# relay.net
KiCad netlist of a schematic drawn in Altium Designer
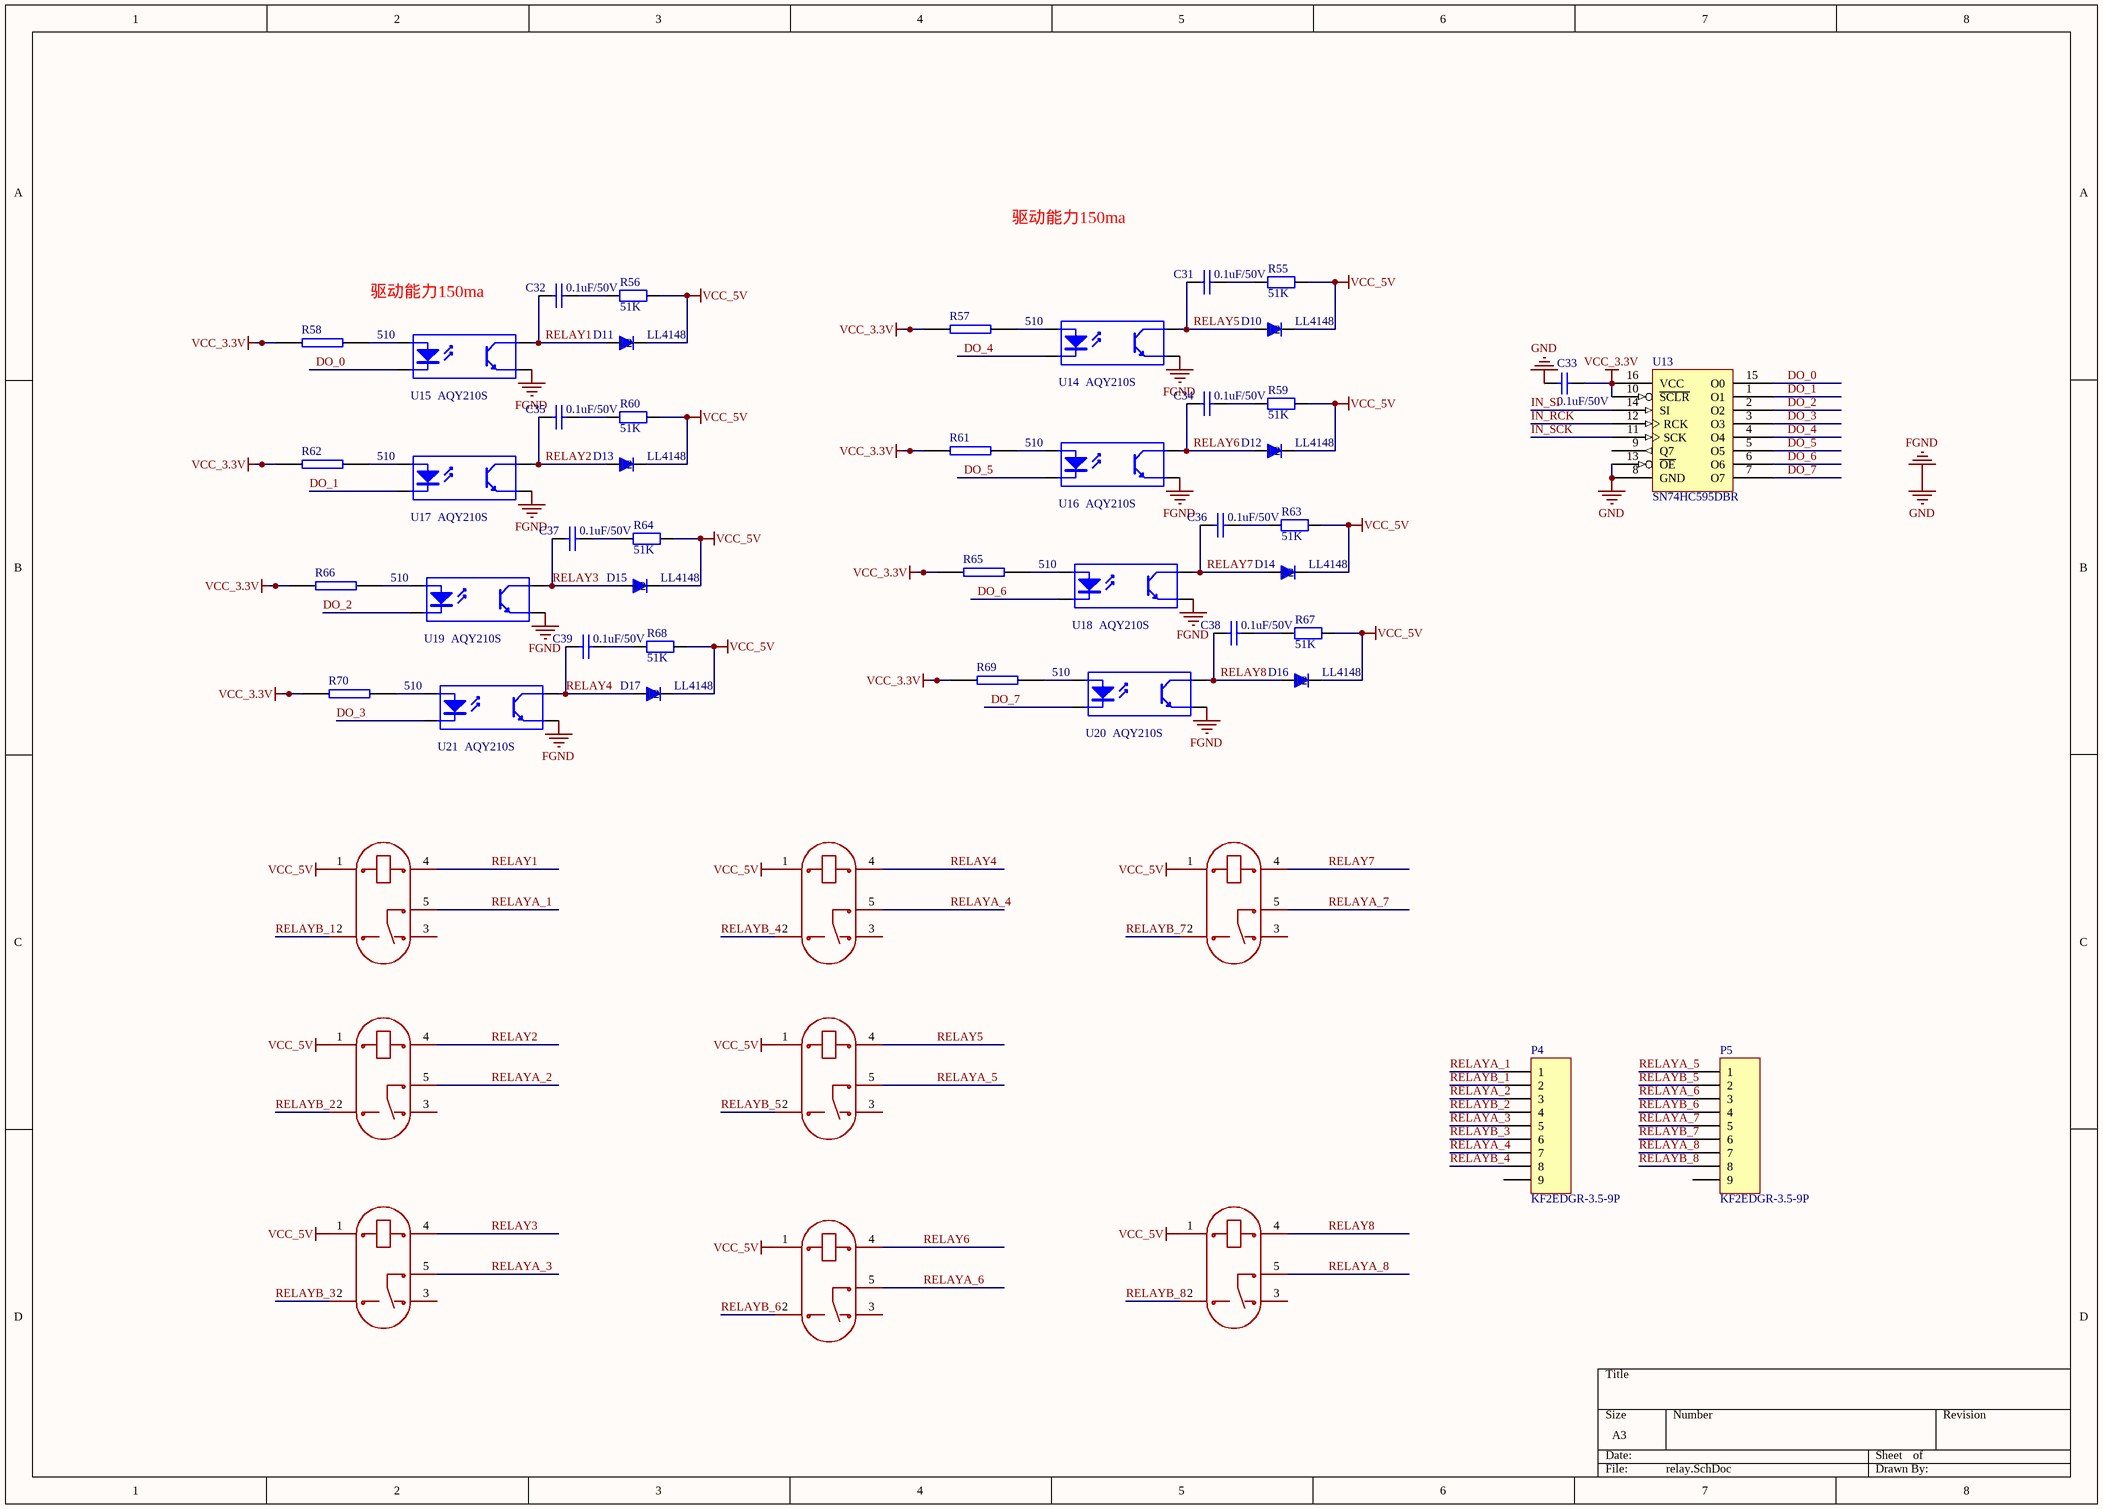
[diagram p0: relay.SchDoc]

(export (version "E")
  (design (tool "Eeschema 10.0.6"))
  (components
    (comp (ref "C31")
      (value "0.1uF/50V")
      (footprint "0603C")
      (description "Capacitor")
      (libsource (lib "*") (part "CAP"))
    )
    (comp (ref "C32")
      (value "0.1uF/50V")
      (footprint "0603C")
      (description "Capacitor")
      (libsource (lib "*") (part "CAP"))
    )
    (comp (ref "C33")
      (value "0.1uF/50V")
      (footprint "0603C")
      (description "Capacitor")
      (libsource (lib "Miscellaneous Devices") (part "Cap"))
    )
    (comp (ref "C34")
      (value "0.1uF/50V")
      (footprint "0603C")
      (description "Capacitor")
      (libsource (lib "*") (part "CAP"))
    )
    (comp (ref "C35")
      (value "0.1uF/50V")
      (footprint "0603C")
      (description "Capacitor")
      (libsource (lib "*") (part "CAP"))
    )
    (comp (ref "C36")
      (value "0.1uF/50V")
      (footprint "0603C")
      (description "Capacitor")
      (libsource (lib "*") (part "CAP"))
    )
    (comp (ref "C37")
      (value "0.1uF/50V")
      (footprint "0603C")
      (description "Capacitor")
      (libsource (lib "*") (part "CAP"))
    )
    (comp (ref "C38")
      (value "0.1uF/50V")
      (footprint "0603C")
      (description "Capacitor")
      (libsource (lib "*") (part "CAP"))
    )
    (comp (ref "C39")
      (value "0.1uF/50V")
      (footprint "0603C")
      (description "Capacitor")
      (libsource (lib "*") (part "CAP"))
    )
    (comp (ref "D10")
      (value "LL4148")
      (footprint "DO-213AB/LL34/MiniMELF")
      (description "VISHAY,LL4148,圆柱体MiniMELF100V/2A,ROHS")
      (libsource (lib "Device2018") (part "LL4148"))
    )
    (comp (ref "D11")
      (value "LL4148")
      (footprint "DO-213AB/LL34/MiniMELF")
      (description "VISHAY,LL4148,圆柱体MiniMELF100V/2A,ROHS")
      (libsource (lib "Device2018") (part "LL4148"))
    )
    (comp (ref "D12")
      (value "LL4148")
      (footprint "DO-213AB/LL34/MiniMELF")
      (description "VISHAY,LL4148,圆柱体MiniMELF100V/2A,ROHS")
      (libsource (lib "Device2018") (part "LL4148"))
    )
    (comp (ref "D13")
      (value "LL4148")
      (footprint "DO-213AB/LL34/MiniMELF")
      (description "VISHAY,LL4148,圆柱体MiniMELF100V/2A,ROHS")
      (libsource (lib "Device2018") (part "LL4148"))
    )
    (comp (ref "D14")
      (value "LL4148")
      (footprint "DO-213AB/LL34/MiniMELF")
      (description "VISHAY,LL4148,圆柱体MiniMELF100V/2A,ROHS")
      (libsource (lib "Device2018") (part "LL4148"))
    )
    (comp (ref "D15")
      (value "LL4148")
      (footprint "DO-213AB/LL34/MiniMELF")
      (description "VISHAY,LL4148,圆柱体MiniMELF100V/2A,ROHS")
      (libsource (lib "Device2018") (part "LL4148"))
    )
    (comp (ref "D16")
      (value "LL4148")
      (footprint "DO-213AB/LL34/MiniMELF")
      (description "VISHAY,LL4148,圆柱体MiniMELF100V/2A,ROHS")
      (libsource (lib "Device2018") (part "LL4148"))
    )
    (comp (ref "D17")
      (value "LL4148")
      (footprint "DO-213AB/LL34/MiniMELF")
      (description "VISHAY,LL4148,圆柱体MiniMELF100V/2A,ROHS")
      (libsource (lib "Device2018") (part "LL4148"))
    )
    (comp (ref "P4")
      (value "KF2EDGR-3.5-9P")
      (footprint "CONN-TH_9P-P3.50_KF2EDGR-3.5-9P:CONN-TH_9P-P3.50_KF2EDGR-3.5-9P")
      (description "Header, 9-Pin")
      (libsource (lib "Miscellaneous Connectors") (part "Header 9"))
    )
    (comp (ref "P5")
      (value "KF2EDGR-3.5-9P")
      (footprint "CONN-TH_9P-P3.50_KF2EDGR-3.5-9P:CONN-TH_9P-P3.50_KF2EDGR-3.5-9P")
      (description "Header, 9-Pin")
      (libsource (lib "Miscellaneous Connectors") (part "Header 9"))
    )
    (comp (ref "R55") (value "51K") (footprint "0603R") (libsource (lib "MQlibrary") (part "Res0805M")))
    (comp (ref "R56") (value "51K") (footprint "0603R") (libsource (lib "MQlibrary") (part "Res0805M")))
    (comp (ref "R57") (value "510") (footprint "0603R") (libsource (lib "*") (part "RES2")))
    (comp (ref "R58") (value "510") (footprint "0603R") (libsource (lib "*") (part "RES2")))
    (comp (ref "R59") (value "51K") (footprint "0603R") (libsource (lib "MQlibrary") (part "Res0805M")))
    (comp (ref "R60") (value "51K") (footprint "0603R") (libsource (lib "MQlibrary") (part "Res0805M")))
    (comp (ref "R61") (value "510") (footprint "0603R") (libsource (lib "*") (part "RES2")))
    (comp (ref "R62") (value "510") (footprint "0603R") (libsource (lib "*") (part "RES2")))
    (comp (ref "R63") (value "51K") (footprint "0603R") (libsource (lib "MQlibrary") (part "Res0805M")))
    (comp (ref "R64") (value "51K") (footprint "0603R") (libsource (lib "MQlibrary") (part "Res0805M")))
    (comp (ref "R65") (value "510") (footprint "0603R") (libsource (lib "*") (part "RES2")))
    (comp (ref "R66") (value "510") (footprint "0603R") (libsource (lib "*") (part "RES2")))
    (comp (ref "R67") (value "51K") (footprint "0603R") (libsource (lib "MQlibrary") (part "Res0805M")))
    (comp (ref "R68") (value "51K") (footprint "0603R") (libsource (lib "MQlibrary") (part "Res0805M")))
    (comp (ref "R69") (value "510") (footprint "0603R") (libsource (lib "*") (part "RES2")))
    (comp (ref "R70") (value "510") (footprint "0603R") (libsource (lib "*") (part "RES2")))
    (comp (ref "RLY1")
      (value "SRD-05VDC-SL-C")
      (footprint "RELAY-TH_SRD-XXVDC-XL-C")
      (libsource (lib "altium-import") (part "root_2_SRD-05VDC-SL-C_"))
    )
    (comp (ref "RLY2")
      (value "SRD-05VDC-SL-C")
      (footprint "RELAY-TH_SRD-XXVDC-XL-C")
      (libsource (lib "altium-import") (part "root_2_SRD-05VDC-SL-C_"))
    )
    (comp (ref "RLY3")
      (value "SRD-05VDC-SL-C")
      (footprint "RELAY-TH_SRD-XXVDC-XL-C")
      (libsource (lib "altium-import") (part "root_2_SRD-05VDC-SL-C_"))
    )
    (comp (ref "RLY4")
      (value "SRD-05VDC-SL-C")
      (footprint "RELAY-TH_SRD-XXVDC-XL-C")
      (libsource (lib "altium-import") (part "root_2_SRD-05VDC-SL-C_"))
    )
    (comp (ref "RLY5")
      (value "SRD-05VDC-SL-C")
      (footprint "RELAY-TH_SRD-XXVDC-XL-C")
      (libsource (lib "altium-import") (part "root_2_SRD-05VDC-SL-C_"))
    )
    (comp (ref "RLY6")
      (value "SRD-05VDC-SL-C")
      (footprint "RELAY-TH_SRD-XXVDC-XL-C")
      (libsource (lib "altium-import") (part "root_2_SRD-05VDC-SL-C_"))
    )
    (comp (ref "RLY7")
      (value "SRD-05VDC-SL-C")
      (footprint "RELAY-TH_SRD-XXVDC-XL-C")
      (libsource (lib "altium-import") (part "root_2_SRD-05VDC-SL-C_"))
    )
    (comp (ref "RLY8")
      (value "SRD-05VDC-SL-C")
      (footprint "RELAY-TH_SRD-XXVDC-XL-C")
      (libsource (lib "altium-import") (part "root_2_SRD-05VDC-SL-C_"))
    )
    (comp (ref "U13") (value "SN74HC595DBR") (footprint "SSOP16") (libsource (lib "DI16") (part "74HC595")))
    (comp (ref "U14")
      (value "AQY210S")
      (footprint "sop4")
      (description "4-Pin Phototransistor Optocoupler")
      (libsource (lib "Miscellaneous Devices") (part "Optoisolator1"))
    )
    (comp (ref "U15")
      (value "AQY210S")
      (footprint "sop4")
      (description "4-Pin Phototransistor Optocoupler")
      (libsource (lib "Miscellaneous Devices") (part "Optoisolator1"))
    )
    (comp (ref "U16")
      (value "AQY210S")
      (footprint "sop4")
      (description "4-Pin Phototransistor Optocoupler")
      (libsource (lib "Miscellaneous Devices") (part "Optoisolator1"))
    )
    (comp (ref "U17")
      (value "AQY210S")
      (footprint "sop4")
      (description "4-Pin Phototransistor Optocoupler")
      (libsource (lib "Miscellaneous Devices") (part "Optoisolator1"))
    )
    (comp (ref "U18")
      (value "AQY210S")
      (footprint "sop4")
      (description "4-Pin Phototransistor Optocoupler")
      (libsource (lib "Miscellaneous Devices") (part "Optoisolator1"))
    )
    (comp (ref "U19")
      (value "AQY210S")
      (footprint "sop4")
      (description "4-Pin Phototransistor Optocoupler")
      (libsource (lib "Miscellaneous Devices") (part "Optoisolator1"))
    )
    (comp (ref "U20")
      (value "AQY210S")
      (footprint "sop4")
      (description "4-Pin Phototransistor Optocoupler")
      (libsource (lib "Miscellaneous Devices") (part "Optoisolator1"))
    )
    (comp (ref "U21")
      (value "AQY210S")
      (footprint "sop4")
      (description "4-Pin Phototransistor Optocoupler")
      (libsource (lib "Miscellaneous Devices") (part "Optoisolator1"))
    )
  )
  (nets
    (net (code "1") (name "/DO_0") (class "Default")
      (node (ref "U13") (pin "15") (pinfunction "O0_15") (pintype "tri_state"))
      (node (ref "U15") (pin "2") (pinfunction "K_2") (pintype "passive"))
    )
    (net (code "2") (name "/DO_1") (class "Default")
      (node (ref "U13") (pin "1") (pinfunction "O1_1") (pintype "tri_state"))
      (node (ref "U17") (pin "2") (pinfunction "K_2") (pintype "passive"))
    )
    (net (code "3") (name "/DO_2") (class "Default")
      (node (ref "U13") (pin "2") (pinfunction "O2_2") (pintype "tri_state"))
      (node (ref "U19") (pin "2") (pinfunction "K_2") (pintype "passive"))
    )
    (net (code "4") (name "/DO_3") (class "Default")
      (node (ref "U13") (pin "3") (pinfunction "O3_3") (pintype "tri_state"))
      (node (ref "U21") (pin "2") (pinfunction "K_2") (pintype "passive"))
    )
    (net (code "5") (name "/DO_4") (class "Default")
      (node (ref "U13") (pin "4") (pinfunction "O4_4") (pintype "tri_state"))
      (node (ref "U14") (pin "2") (pinfunction "K_2") (pintype "passive"))
    )
    (net (code "6") (name "/DO_5") (class "Default")
      (node (ref "U13") (pin "5") (pinfunction "O5_5") (pintype "tri_state"))
      (node (ref "U16") (pin "2") (pinfunction "K_2") (pintype "passive"))
    )
    (net (code "7") (name "/DO_6") (class "Default")
      (node (ref "U13") (pin "6") (pinfunction "O6_6") (pintype "tri_state"))
      (node (ref "U18") (pin "2") (pinfunction "K_2") (pintype "passive"))
    )
    (net (code "8") (name "/DO_7") (class "Default")
      (node (ref "U13") (pin "7") (pinfunction "O7_7") (pintype "tri_state"))
      (node (ref "U20") (pin "2") (pinfunction "K_2") (pintype "passive"))
    )
    (net (code "9") (name "/IN_RCK") (class "Default")
      (node (ref "U13") (pin "12") (pinfunction "RCK_12") (pintype "input"))
    )
    (net (code "10") (name "/IN_SCK") (class "Default")
      (node (ref "U13") (pin "11") (pinfunction "SCK_11") (pintype "input"))
    )
    (net (code "11") (name "/IN_SI") (class "Default")
      (node (ref "U13") (pin "14") (pinfunction "SI_14") (pintype "input"))
    )
    (net (code "12") (name "/RELAY1") (class "Default")
      (node (ref "C32") (pin "1") (pinfunction "1_1") (pintype "passive"))
      (node (ref "D11") (pin "1") (pinfunction "2_1") (pintype "passive"))
      (node (ref "RLY1") (pin "4") (pinfunction "4_4") (pintype "passive"))
      (node (ref "U15") (pin "4") (pinfunction "C_4") (pintype "passive"))
    )
    (net (code "13") (name "/RELAY2") (class "Default")
      (node (ref "C35") (pin "1") (pinfunction "1_1") (pintype "passive"))
      (node (ref "D13") (pin "1") (pinfunction "2_1") (pintype "passive"))
      (node (ref "RLY4") (pin "4") (pinfunction "4_4") (pintype "passive"))
      (node (ref "U17") (pin "4") (pinfunction "C_4") (pintype "passive"))
    )
    (net (code "14") (name "/RELAY3") (class "Default")
      (node (ref "C37") (pin "1") (pinfunction "1_1") (pintype "passive"))
      (node (ref "D15") (pin "1") (pinfunction "2_1") (pintype "passive"))
      (node (ref "RLY6") (pin "4") (pinfunction "4_4") (pintype "passive"))
      (node (ref "U19") (pin "4") (pinfunction "C_4") (pintype "passive"))
    )
    (net (code "15") (name "/RELAY4") (class "Default")
      (node (ref "C39") (pin "1") (pinfunction "1_1") (pintype "passive"))
      (node (ref "D17") (pin "1") (pinfunction "2_1") (pintype "passive"))
      (node (ref "RLY2") (pin "4") (pinfunction "4_4") (pintype "passive"))
      (node (ref "U21") (pin "4") (pinfunction "C_4") (pintype "passive"))
    )
    (net (code "16") (name "/RELAY5") (class "Default")
      (node (ref "C31") (pin "1") (pinfunction "1_1") (pintype "passive"))
      (node (ref "D10") (pin "1") (pinfunction "2_1") (pintype "passive"))
      (node (ref "RLY5") (pin "4") (pinfunction "4_4") (pintype "passive"))
      (node (ref "U14") (pin "4") (pinfunction "C_4") (pintype "passive"))
    )
    (net (code "17") (name "/RELAY6") (class "Default")
      (node (ref "C34") (pin "1") (pinfunction "1_1") (pintype "passive"))
      (node (ref "D12") (pin "1") (pinfunction "2_1") (pintype "passive"))
      (node (ref "RLY8") (pin "4") (pinfunction "4_4") (pintype "passive"))
      (node (ref "U16") (pin "4") (pinfunction "C_4") (pintype "passive"))
    )
    (net (code "18") (name "/RELAY7") (class "Default")
      (node (ref "C36") (pin "1") (pinfunction "1_1") (pintype "passive"))
      (node (ref "D14") (pin "1") (pinfunction "2_1") (pintype "passive"))
      (node (ref "RLY3") (pin "4") (pinfunction "4_4") (pintype "passive"))
      (node (ref "U18") (pin "4") (pinfunction "C_4") (pintype "passive"))
    )
    (net (code "19") (name "/RELAY8") (class "Default")
      (node (ref "C38") (pin "1") (pinfunction "1_1") (pintype "passive"))
      (node (ref "D16") (pin "1") (pinfunction "2_1") (pintype "passive"))
      (node (ref "RLY7") (pin "4") (pinfunction "4_4") (pintype "passive"))
      (node (ref "U20") (pin "4") (pinfunction "C_4") (pintype "passive"))
    )
    (net (code "20") (name "/RELAYA_1") (class "Default")
      (node (ref "P4") (pin "1") (pinfunction "1_1") (pintype "passive"))
      (node (ref "RLY1") (pin "5") (pinfunction "5_5") (pintype "passive"))
    )
    (net (code "21") (name "/RELAYA_2") (class "Default")
      (node (ref "P4") (pin "3") (pinfunction "3_3") (pintype "passive"))
      (node (ref "RLY4") (pin "5") (pinfunction "5_5") (pintype "passive"))
    )
    (net (code "22") (name "/RELAYA_3") (class "Default")
      (node (ref "P4") (pin "5") (pinfunction "5_5") (pintype "passive"))
      (node (ref "RLY6") (pin "5") (pinfunction "5_5") (pintype "passive"))
    )
    (net (code "23") (name "/RELAYA_4") (class "Default")
      (node (ref "P4") (pin "7") (pinfunction "7_7") (pintype "passive"))
      (node (ref "RLY2") (pin "5") (pinfunction "5_5") (pintype "passive"))
    )
    (net (code "24") (name "/RELAYA_5") (class "Default")
      (node (ref "P5") (pin "1") (pinfunction "1_1") (pintype "passive"))
      (node (ref "RLY5") (pin "5") (pinfunction "5_5") (pintype "passive"))
    )
    (net (code "25") (name "/RELAYA_6") (class "Default")
      (node (ref "P5") (pin "3") (pinfunction "3_3") (pintype "passive"))
      (node (ref "RLY8") (pin "5") (pinfunction "5_5") (pintype "passive"))
    )
    (net (code "26") (name "/RELAYA_7") (class "Default")
      (node (ref "P5") (pin "5") (pinfunction "5_5") (pintype "passive"))
      (node (ref "RLY3") (pin "5") (pinfunction "5_5") (pintype "passive"))
    )
    (net (code "27") (name "/RELAYA_8") (class "Default")
      (node (ref "P5") (pin "7") (pinfunction "7_7") (pintype "passive"))
      (node (ref "RLY7") (pin "5") (pinfunction "5_5") (pintype "passive"))
    )
    (net (code "28") (name "/RELAYB_1") (class "Default")
      (node (ref "P4") (pin "2") (pinfunction "2_2") (pintype "passive"))
      (node (ref "RLY1") (pin "2") (pinfunction "2_2") (pintype "passive"))
    )
    (net (code "29") (name "/RELAYB_2") (class "Default")
      (node (ref "P4") (pin "4") (pinfunction "4_4") (pintype "passive"))
      (node (ref "RLY4") (pin "2") (pinfunction "2_2") (pintype "passive"))
    )
    (net (code "30") (name "/RELAYB_3") (class "Default")
      (node (ref "P4") (pin "6") (pinfunction "6_6") (pintype "passive"))
      (node (ref "RLY6") (pin "2") (pinfunction "2_2") (pintype "passive"))
    )
    (net (code "31") (name "/RELAYB_4") (class "Default")
      (node (ref "P4") (pin "8") (pinfunction "8_8") (pintype "passive"))
      (node (ref "RLY2") (pin "2") (pinfunction "2_2") (pintype "passive"))
    )
    (net (code "32") (name "/RELAYB_5") (class "Default")
      (node (ref "P5") (pin "2") (pinfunction "2_2") (pintype "passive"))
      (node (ref "RLY5") (pin "2") (pinfunction "2_2") (pintype "passive"))
    )
    (net (code "33") (name "/RELAYB_6") (class "Default")
      (node (ref "P5") (pin "4") (pinfunction "4_4") (pintype "passive"))
      (node (ref "RLY8") (pin "2") (pinfunction "2_2") (pintype "passive"))
    )
    (net (code "34") (name "/RELAYB_7") (class "Default")
      (node (ref "P5") (pin "6") (pinfunction "6_6") (pintype "passive"))
      (node (ref "RLY3") (pin "2") (pinfunction "2_2") (pintype "passive"))
    )
    (net (code "35") (name "/RELAYB_8") (class "Default")
      (node (ref "P5") (pin "8") (pinfunction "8_8") (pintype "passive"))
      (node (ref "RLY7") (pin "2") (pinfunction "2_2") (pintype "passive"))
    )
    (net (code "36") (name "FGND") (class "Default")
      (node (ref "C33") (pin "2") (pinfunction "2_2") (pintype "passive"))
      (node (ref "U13") (pin "13") (pinfunction "~{OE}_13") (pintype "input"))
      (node (ref "U13") (pin "8") (pinfunction "GND_8") (pintype "power_in"))
      (node (ref "U14") (pin "3") (pinfunction "E_3") (pintype "passive"))
      (node (ref "U15") (pin "3") (pinfunction "E_3") (pintype "passive"))
      (node (ref "U16") (pin "3") (pinfunction "E_3") (pintype "passive"))
      (node (ref "U17") (pin "3") (pinfunction "E_3") (pintype "passive"))
      (node (ref "U18") (pin "3") (pinfunction "E_3") (pintype "passive"))
      (node (ref "U19") (pin "3") (pinfunction "E_3") (pintype "passive"))
      (node (ref "U20") (pin "3") (pinfunction "E_3") (pintype "passive"))
      (node (ref "U21") (pin "3") (pinfunction "E_3") (pintype "passive"))
    )
    (net (code "37") (name "Net-(C31-Pad2)") (class "Default")
      (node (ref "C31") (pin "2") (pinfunction "2_2") (pintype "passive"))
      (node (ref "R55") (pin "1") (pinfunction "1_1") (pintype "passive"))
    )
    (net (code "38") (name "Net-(C32-Pad2)") (class "Default")
      (node (ref "C32") (pin "2") (pinfunction "2_2") (pintype "passive"))
      (node (ref "R56") (pin "1") (pinfunction "1_1") (pintype "passive"))
    )
    (net (code "39") (name "Net-(C34-Pad2)") (class "Default")
      (node (ref "C34") (pin "2") (pinfunction "2_2") (pintype "passive"))
      (node (ref "R59") (pin "1") (pinfunction "1_1") (pintype "passive"))
    )
    (net (code "40") (name "Net-(C35-Pad2)") (class "Default")
      (node (ref "C35") (pin "2") (pinfunction "2_2") (pintype "passive"))
      (node (ref "R60") (pin "1") (pinfunction "1_1") (pintype "passive"))
    )
    (net (code "41") (name "Net-(C36-Pad2)") (class "Default")
      (node (ref "C36") (pin "2") (pinfunction "2_2") (pintype "passive"))
      (node (ref "R63") (pin "1") (pinfunction "1_1") (pintype "passive"))
    )
    (net (code "42") (name "Net-(C37-Pad2)") (class "Default")
      (node (ref "C37") (pin "2") (pinfunction "2_2") (pintype "passive"))
      (node (ref "R64") (pin "1") (pinfunction "1_1") (pintype "passive"))
    )
    (net (code "43") (name "Net-(C38-Pad2)") (class "Default")
      (node (ref "C38") (pin "2") (pinfunction "2_2") (pintype "passive"))
      (node (ref "R67") (pin "1") (pinfunction "1_1") (pintype "passive"))
    )
    (net (code "44") (name "Net-(C39-Pad2)") (class "Default")
      (node (ref "C39") (pin "2") (pinfunction "2_2") (pintype "passive"))
      (node (ref "R68") (pin "1") (pinfunction "1_1") (pintype "passive"))
    )
    (net (code "45") (name "Net-(U14-A)") (class "Default")
      (node (ref "R57") (pin "1") (pinfunction "1_1") (pintype "passive"))
      (node (ref "U14") (pin "1") (pinfunction "A_1") (pintype "passive"))
    )
    (net (code "46") (name "Net-(U15-A)") (class "Default")
      (node (ref "R58") (pin "1") (pinfunction "1_1") (pintype "passive"))
      (node (ref "U15") (pin "1") (pinfunction "A_1") (pintype "passive"))
    )
    (net (code "47") (name "Net-(U16-A)") (class "Default")
      (node (ref "R61") (pin "1") (pinfunction "1_1") (pintype "passive"))
      (node (ref "U16") (pin "1") (pinfunction "A_1") (pintype "passive"))
    )
    (net (code "48") (name "Net-(U17-A)") (class "Default")
      (node (ref "R62") (pin "1") (pinfunction "1_1") (pintype "passive"))
      (node (ref "U17") (pin "1") (pinfunction "A_1") (pintype "passive"))
    )
    (net (code "49") (name "Net-(U18-A)") (class "Default")
      (node (ref "R65") (pin "1") (pinfunction "1_1") (pintype "passive"))
      (node (ref "U18") (pin "1") (pinfunction "A_1") (pintype "passive"))
    )
    (net (code "50") (name "Net-(U19-A)") (class "Default")
      (node (ref "R66") (pin "1") (pinfunction "1_1") (pintype "passive"))
      (node (ref "U19") (pin "1") (pinfunction "A_1") (pintype "passive"))
    )
    (net (code "51") (name "Net-(U20-A)") (class "Default")
      (node (ref "R69") (pin "1") (pinfunction "1_1") (pintype "passive"))
      (node (ref "U20") (pin "1") (pinfunction "A_1") (pintype "passive"))
    )
    (net (code "52") (name "Net-(U21-A)") (class "Default")
      (node (ref "R70") (pin "1") (pinfunction "1_1") (pintype "passive"))
      (node (ref "U21") (pin "1") (pinfunction "A_1") (pintype "passive"))
    )
    (net (code "53") (name "VCC_3.3V") (class "Default")
      (node (ref "C33") (pin "1") (pinfunction "1_1") (pintype "passive"))
      (node (ref "R57") (pin "2") (pinfunction "2_2") (pintype "passive"))
      (node (ref "R58") (pin "2") (pinfunction "2_2") (pintype "passive"))
      (node (ref "R61") (pin "2") (pinfunction "2_2") (pintype "passive"))
      (node (ref "R62") (pin "2") (pinfunction "2_2") (pintype "passive"))
      (node (ref "R65") (pin "2") (pinfunction "2_2") (pintype "passive"))
      (node (ref "R66") (pin "2") (pinfunction "2_2") (pintype "passive"))
      (node (ref "R69") (pin "2") (pinfunction "2_2") (pintype "passive"))
      (node (ref "R70") (pin "2") (pinfunction "2_2") (pintype "passive"))
      (node (ref "U13") (pin "10") (pinfunction "~{SCLR}_10") (pintype "input"))
      (node (ref "U13") (pin "16") (pinfunction "VCC_16") (pintype "power_in"))
    )
    (net (code "54") (name "VCC_5V") (class "Default")
      (node (ref "D10") (pin "2") (pinfunction "1_2") (pintype "passive"))
      (node (ref "D11") (pin "2") (pinfunction "1_2") (pintype "passive"))
      (node (ref "D12") (pin "2") (pinfunction "1_2") (pintype "passive"))
      (node (ref "D13") (pin "2") (pinfunction "1_2") (pintype "passive"))
      (node (ref "D14") (pin "2") (pinfunction "1_2") (pintype "passive"))
      (node (ref "D15") (pin "2") (pinfunction "1_2") (pintype "passive"))
      (node (ref "D16") (pin "2") (pinfunction "1_2") (pintype "passive"))
      (node (ref "D17") (pin "2") (pinfunction "1_2") (pintype "passive"))
      (node (ref "R55") (pin "2") (pinfunction "2_2") (pintype "passive"))
      (node (ref "R56") (pin "2") (pinfunction "2_2") (pintype "passive"))
      (node (ref "R59") (pin "2") (pinfunction "2_2") (pintype "passive"))
      (node (ref "R60") (pin "2") (pinfunction "2_2") (pintype "passive"))
      (node (ref "R63") (pin "2") (pinfunction "2_2") (pintype "passive"))
      (node (ref "R64") (pin "2") (pinfunction "2_2") (pintype "passive"))
      (node (ref "R67") (pin "2") (pinfunction "2_2") (pintype "passive"))
      (node (ref "R68") (pin "2") (pinfunction "2_2") (pintype "passive"))
      (node (ref "RLY1") (pin "1") (pinfunction "1_1") (pintype "passive"))
      (node (ref "RLY2") (pin "1") (pinfunction "1_1") (pintype "passive"))
      (node (ref "RLY3") (pin "1") (pinfunction "1_1") (pintype "passive"))
      (node (ref "RLY4") (pin "1") (pinfunction "1_1") (pintype "passive"))
      (node (ref "RLY5") (pin "1") (pinfunction "1_1") (pintype "passive"))
      (node (ref "RLY6") (pin "1") (pinfunction "1_1") (pintype "passive"))
      (node (ref "RLY7") (pin "1") (pinfunction "1_1") (pintype "passive"))
      (node (ref "RLY8") (pin "1") (pinfunction "1_1") (pintype "passive"))
    )
    (net (code "55") (name "unconnected-(P4-Pad9)") (class "Default")
      (node (ref "P4") (pin "9") (pinfunction "9_9") (pintype "passive"))
    )
    (net (code "56") (name "unconnected-(P5-Pad9)") (class "Default")
      (node (ref "P5") (pin "9") (pinfunction "9_9") (pintype "passive"))
    )
    (net (code "57") (name "unconnected-(RLY1-Pad3)") (class "Default")
      (node (ref "RLY1") (pin "3") (pinfunction "3_3") (pintype "passive"))
    )
    (net (code "58") (name "unconnected-(RLY2-Pad3)") (class "Default")
      (node (ref "RLY2") (pin "3") (pinfunction "3_3") (pintype "passive"))
    )
    (net (code "59") (name "unconnected-(RLY3-Pad3)") (class "Default")
      (node (ref "RLY3") (pin "3") (pinfunction "3_3") (pintype "passive"))
    )
    (net (code "60") (name "unconnected-(RLY4-Pad3)") (class "Default")
      (node (ref "RLY4") (pin "3") (pinfunction "3_3") (pintype "passive"))
    )
    (net (code "61") (name "unconnected-(RLY5-Pad3)") (class "Default")
      (node (ref "RLY5") (pin "3") (pinfunction "3_3") (pintype "passive"))
    )
    (net (code "62") (name "unconnected-(RLY6-Pad3)") (class "Default")
      (node (ref "RLY6") (pin "3") (pinfunction "3_3") (pintype "passive"))
    )
    (net (code "63") (name "unconnected-(RLY7-Pad3)") (class "Default")
      (node (ref "RLY7") (pin "3") (pinfunction "3_3") (pintype "passive"))
    )
    (net (code "64") (name "unconnected-(RLY8-Pad3)") (class "Default")
      (node (ref "RLY8") (pin "3") (pinfunction "3_3") (pintype "passive"))
    )
    (net (code "65") (name "unconnected-(U13-Q7-Pad9)") (class "Default")
      (node (ref "U13") (pin "9") (pinfunction "Q7_9") (pintype "output"))
    )
  )
)
